# AHT20_DEMO_V1_5.net
KiCad netlist of a schematic drawn in Altium Designer
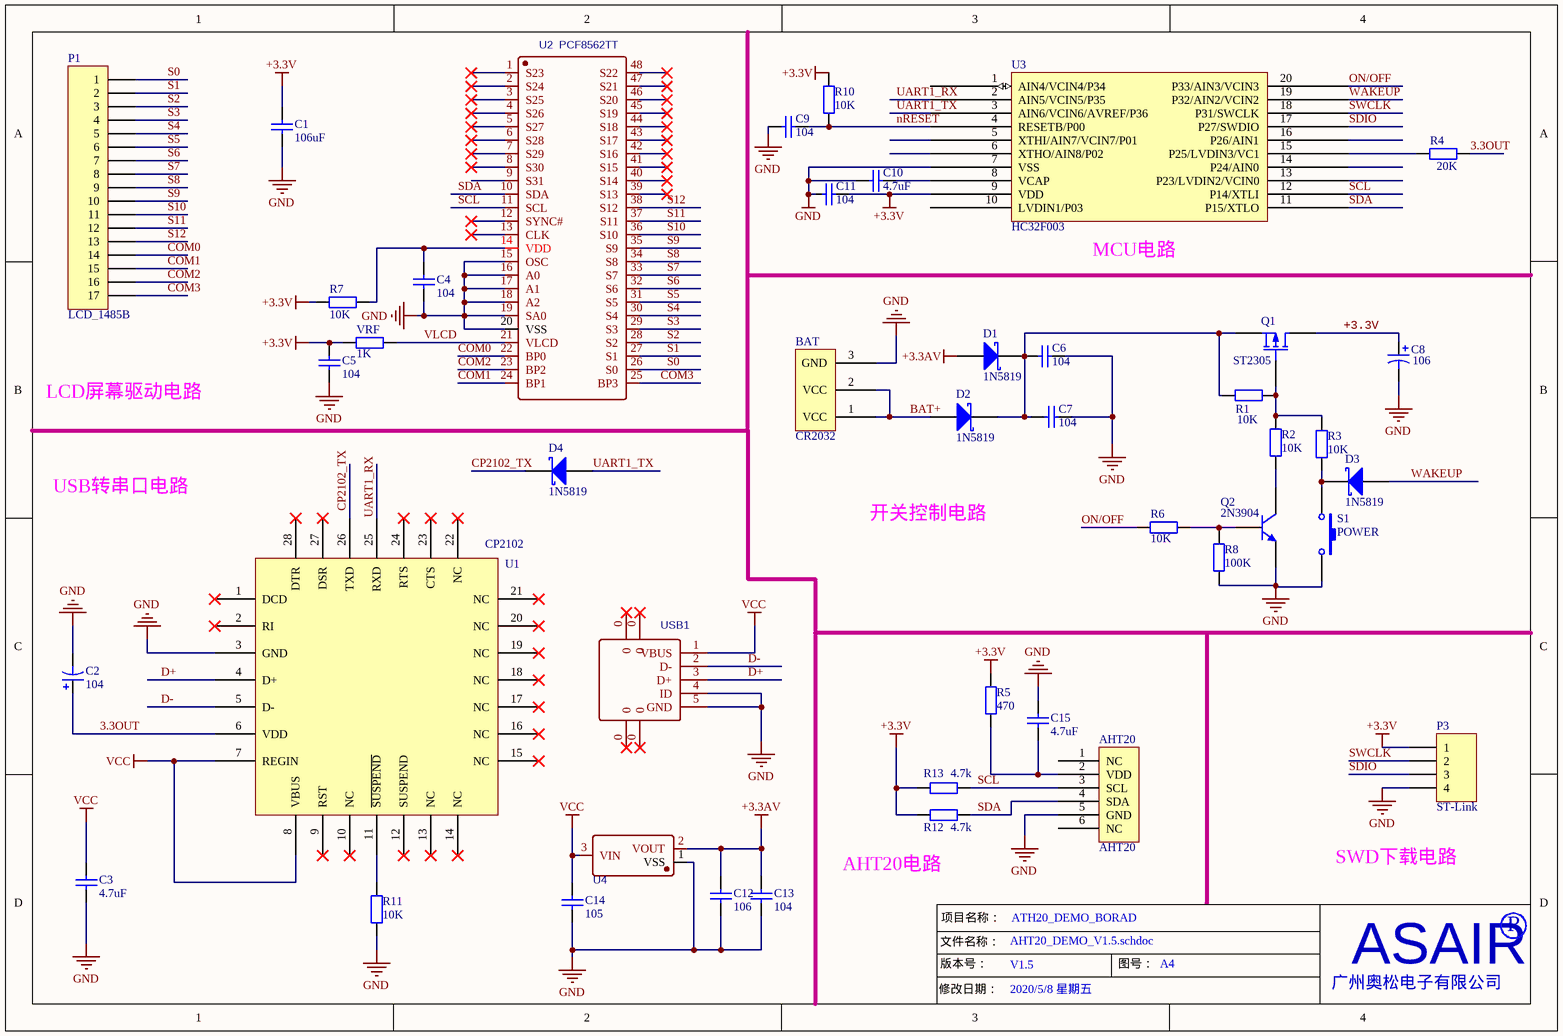
[diagram p0: AHT20_DEMO_V1.5.schdoc]

(export (version "E")
  (design (tool "Eeschema 10.0.6"))
  (components
    (comp (ref "AHT20") (value "AHT20") (footprint "AHT20") (libsource (lib "Schlib1") (part "AHT20")))
    (comp (ref "BAT") (value "CR2032") (footprint "CR2032-W") (libsource (lib "Schlib1") (part "CR2032")))
    (comp (ref "C1")
      (value "106uF")
      (footprint "0603C")
      (description "Capacitor")
      (fields (field (name "PUBLISHER") "Altium Limited"))
      (libsource (lib "Miscellaneous Devices") (part "Cap"))
    )
    (comp (ref "C2")
      (value "104")
      (footprint "0603c")
      (description "Polarized Capacitor (Radial)")
      (fields (field (name "PUBLISHER") "Altium Limited"))
      (libsource (lib "*") (part "Cap Pol1"))
    )
    (comp (ref "C3")
      (value "4.7uF")
      (footprint "0603C")
      (description "Capacitor")
      (fields (field (name "PUBLISHER") "Altium Limited"))
      (libsource (lib "Miscellaneous Devices") (part "Cap"))
    )
    (comp (ref "C4")
      (value "104")
      (footprint "0603C")
      (description "Capacitor")
      (fields (field (name "PUBLISHER") "Altium Limited"))
      (libsource (lib "Miscellaneous Devices") (part "Cap"))
    )
    (comp (ref "C5")
      (value "104")
      (footprint "0603C")
      (description "Capacitor")
      (fields (field (name "PUBLISHER") "Altium Limited"))
      (libsource (lib "Miscellaneous Devices") (part "Cap"))
    )
    (comp (ref "C6")
      (value "104")
      (footprint "0603C")
      (description "Capacitor")
      (fields (field (name "PUBLISHER") "Altium Limited"))
      (libsource (lib "Miscellaneous Devices") (part "Cap"))
    )
    (comp (ref "C7")
      (value "104")
      (footprint "0603C")
      (description "Capacitor")
      (fields (field (name "PUBLISHER") "Altium Limited"))
      (libsource (lib "Miscellaneous Devices") (part "Cap"))
    )
    (comp (ref "C8")
      (value "106")
      (footprint "0603c")
      (description "Polarized Capacitor (Radial)")
      (fields (field (name "PUBLISHER") "Altium Limited"))
      (libsource (lib "*") (part "Cap Pol1"))
    )
    (comp (ref "C9")
      (value "104")
      (footprint "0603C")
      (description "Capacitor")
      (fields (field (name "PUBLISHER") "Altium Limited"))
      (libsource (lib "Miscellaneous Devices") (part "Cap"))
    )
    (comp (ref "C10")
      (value "4.7uF")
      (footprint "0603C")
      (description "Capacitor")
      (fields (field (name "PUBLISHER") "Altium Limited"))
      (libsource (lib "Miscellaneous Devices") (part "Cap"))
    )
    (comp (ref "C11")
      (value "104")
      (footprint "0603C")
      (description "Capacitor")
      (fields (field (name "PUBLISHER") "Altium Limited"))
      (libsource (lib "Miscellaneous Devices") (part "Cap"))
    )
    (comp (ref "C12")
      (value "106")
      (footprint "0603C")
      (description "Capacitor")
      (fields (field (name "Comment") "104") (field (name "PUBLISHER") "Altium Limited"))
      (libsource (lib "Miscellaneous Devices") (part "Cap"))
    )
    (comp (ref "C13")
      (value "104")
      (footprint "0603C")
      (description "Capacitor")
      (fields (field (name "PUBLISHER") "Altium Limited"))
      (libsource (lib "Miscellaneous Devices") (part "Cap"))
    )
    (comp (ref "C14")
      (value "105")
      (footprint "0603C")
      (description "Capacitor")
      (fields (field (name "Comment") "104") (field (name "PUBLISHER") "Altium Limited"))
      (libsource (lib "Miscellaneous Devices") (part "Cap"))
    )
    (comp (ref "C15")
      (value "4.7uF")
      (footprint "0603C")
      (description "Capacitor")
      (fields (field (name "PUBLISHER") "Altium Limited"))
      (libsource (lib "Miscellaneous Devices") (part "Cap"))
    )
    (comp (ref "D1")
      (value "1N5819")
      (footprint "0805-LED")
      (description "Schottky Diode")
      (fields (field (name "PUBLISHER") "Altium Limited"))
      (libsource (lib "*") (part "D Schottky"))
    )
    (comp (ref "D2")
      (value "1N5819")
      (footprint "0805-LED")
      (description "Schottky Diode")
      (fields (field (name "PUBLISHER") "Altium Limited"))
      (libsource (lib "*") (part "D Schottky"))
    )
    (comp (ref "D3")
      (value "1N5819")
      (footprint "0805-LED")
      (description "Schottky Diode")
      (fields (field (name "PUBLISHER") "Altium Limited"))
      (libsource (lib "*") (part "D Schottky"))
    )
    (comp (ref "D4")
      (value "1N5819")
      (footprint "0805-LED")
      (description "Schottky Diode")
      (fields (field (name "PUBLISHER") "Altium Limited"))
      (libsource (lib "*") (part "D Schottky"))
    )
    (comp (ref "P1")
      (value "LCD_1485B")
      (footprint "LCD1485B")
      (description "Header, 17-Pin")
      (fields (field (name "PUBLISHER") "Altium Limited"))
      (libsource (lib "AW1485B") (part "LED1485B"))
    )
    (comp (ref "P3")
      (value "ST-Link")
      (footprint "DIP-5")
      (description "Header, 4-Pin")
      (fields (field (name "PUBLISHER") "Altium Limited"))
      (libsource (lib "*") (part "Header 4"))
    )
    (comp (ref "Q1")
      (value "ST2305")
      (footprint "SOt23")
      (description "P-Channel MOSFET")
      (fields (field (name "PUBLISHER") "Altium Limited"))
      (libsource (lib "Miscellaneous Devices") (part "MOSFET-P"))
    )
    (comp (ref "Q2")
      (value "2N3904")
      (footprint "SOt23")
      (description "NPN General Purpose Amplifier")
      (fields (field (name "PUBLISHER") "Altium Limited"))
      (libsource (lib "Miscellaneous Devices") (part "2N3904"))
    )
    (comp (ref "R1")
      (value "10K")
      (footprint "0603R")
      (description "Resistor")
      (fields (field (name "PUBLISHER") "Altium Limited"))
      (libsource (lib "") (part "Res2_6"))
    )
    (comp (ref "R2")
      (value "10K")
      (footprint "0603R")
      (description "Resistor")
      (fields (field (name "PUBLISHER") "Altium Limited"))
      (libsource (lib "") (part "Res2_5"))
    )
    (comp (ref "R3")
      (value "10K")
      (footprint "0603R")
      (description "Resistor")
      (fields (field (name "PUBLISHER") "Altium Limited"))
      (libsource (lib "") (part "Res2_5"))
    )
    (comp (ref "R4")
      (value "20K")
      (footprint "0603R")
      (description "Resistor")
      (fields (field (name "PUBLISHER") "Altium Limited"))
      (libsource (lib "") (part "Res2_1"))
    )
    (comp (ref "R5")
      (value "470")
      (footprint "0603R")
      (description "Resistor")
      (fields (field (name "PUBLISHER") "Altium Limited"))
      (libsource (lib "") (part "Res2_4"))
    )
    (comp (ref "R6")
      (value "10K")
      (footprint "0603R")
      (description "Resistor")
      (fields (field (name "PUBLISHER") "Altium Limited"))
      (libsource (lib "") (part "Res2_1"))
    )
    (comp (ref "R7")
      (value "10K")
      (footprint "0603R")
      (description "Resistor")
      (fields (field (name "PUBLISHER") "Altium Limited"))
      (libsource (lib "") (part "Res2_5"))
    )
    (comp (ref "R8")
      (value "100K")
      (footprint "0603R")
      (description "Resistor")
      (fields (field (name "PUBLISHER") "Altium Limited"))
      (libsource (lib "") (part "Res2_5"))
    )
    (comp (ref "R10")
      (value "10K")
      (footprint "0603R")
      (description "Resistor")
      (fields (field (name "PUBLISHER") "Altium Limited"))
      (libsource (lib "") (part "Res2_3"))
    )
    (comp (ref "R11")
      (value "10K")
      (footprint "0603R")
      (description "Resistor")
      (fields (field (name "PUBLISHER") "Altium Limited"))
      (libsource (lib "") (part "Res2_2"))
    )
    (comp (ref "R12")
      (value "4.7k")
      (footprint "0603R")
      (description "Resistor")
      (fields (field (name "PUBLISHER") "Altium Limited"))
      (libsource (lib "Miscellaneous Devices") (part "Res2"))
    )
    (comp (ref "R13")
      (value "4.7k")
      (footprint "0603R")
      (description "Resistor")
      (fields (field (name "PUBLISHER") "Altium Limited"))
      (libsource (lib "Miscellaneous Devices") (part "Res2"))
    )
    (comp (ref "S1")
      (value "POWER")
      (footprint "KEY")
      (description "Switch")
      (fields (field (name "PUBLISHER") "Altium Limited"))
      (libsource (lib "*") (part "SW-PB"))
    )
    (comp (ref "U1") (value "CP2102") (footprint "CP2102") (libsource (lib "RLM600") (part "CP2102_1")))
    (comp (ref "U2")
      (value "PCF8562TT")
      (footprint "PCF8562TT")
      (fields (field (name "BOM_SUPPLIER PART") "C52805"))
      (libsource (lib "altium-import") (part "root_0_PCF8562TT_"))
    )
    (comp (ref "U3")
      (value "HC32F003")
      (footprint "TSSOP20")
      (description "MCU")
      (libsource (lib "AF5010-V5.0") (part "HC32F003"))
    )
    (comp (ref "U4")
      (value "XC6206P282MR_C347374")
      (footprint "XC6206")
      (fields
        (field (name "BOM_SUPPLIER PART") "C347374")
        (field (name "BOM_MANUFACTURER PART") "XC6206P282MR")
        (field (name "CONTRIBUTOR") "LCSC")
      )
      (libsource (lib "altium-import") (part "root_2_XC6206P282MR_C347374_"))
    )
    (comp (ref "USB1")
      (value "micro 5P_C77238")
      (footprint "USB")
      (fields (field (name "BOM_SUPPLIER PART") "C77238") (field (name "CONTRIBUTOR") "立创EDA官方封装库"))
      (libsource (lib "altium-import") (part "root_0_mirrored_micro 5P_C77238_"))
    )
    (comp (ref "VRF")
      (value "1K")
      (footprint "0603R")
      (description "Resistor")
      (fields (field (name "PUBLISHER") "Altium Limited"))
      (libsource (lib "Miscellaneous Devices") (part "Res2"))
    )
  )
  (nets
    (net (code "1") (name "+3.3AV") (class "Default")
      (node (ref "C12") (pin "2") (pinfunction "2_2") (pintype "passive"))
      (node (ref "C13") (pin "2") (pinfunction "2_2") (pintype "passive"))
      (node (ref "D1") (pin "1") (pinfunction "A_1") (pintype "passive"))
      (node (ref "U4") (pin "2") (pinfunction "VOUT_2") (pintype "passive"))
    )
    (net (code "2") (name "+3.3V") (class "Default")
      (node (ref "C1") (pin "2") (pinfunction "2_2") (pintype "passive"))
      (node (ref "C11") (pin "2") (pinfunction "2_2") (pintype "passive"))
      (node (ref "C5") (pin "2") (pinfunction "2_2") (pintype "passive"))
      (node (ref "C8") (pin "1") (pinfunction "1_1") (pintype "passive"))
      (node (ref "P3") (pin "1") (pinfunction "1_1") (pintype "passive"))
      (node (ref "Q1") (pin "1") (pinfunction "D_1") (pintype "passive"))
      (node (ref "R10") (pin "1") (pinfunction "1_1") (pintype "passive"))
      (node (ref "R12") (pin "1") (pinfunction "1_1") (pintype "passive"))
      (node (ref "R13") (pin "1") (pinfunction "1_1") (pintype "passive"))
      (node (ref "R5") (pin "2") (pinfunction "2_2") (pintype "passive"))
      (node (ref "R7") (pin "2") (pinfunction "2_2") (pintype "passive"))
      (node (ref "U3") (pin "9") (pinfunction "VDD_9") (pintype "passive"))
      (node (ref "VRF") (pin "1") (pinfunction "1_1") (pintype "passive"))
    )
    (net (code "3") (name "/3.3OUT") (class "Default")
      (node (ref "C2") (pin "1") (pinfunction "1_1") (pintype "passive"))
      (node (ref "R4") (pin "2") (pinfunction "2_2") (pintype "passive"))
      (node (ref "U1") (pin "6") (pinfunction "VDD_6") (pintype "passive"))
    )
    (net (code "4") (name "/BAT+") (class "Default")
      (node (ref "BAT") (pin "1") (pinfunction "VCC_1") (pintype "passive"))
      (node (ref "BAT") (pin "2") (pinfunction "VCC_2") (pintype "passive"))
      (node (ref "D2") (pin "1") (pinfunction "A_1") (pintype "passive"))
    )
    (net (code "5") (name "/COM0") (class "Default")
      (node (ref "P1") (pin "14") (pinfunction "14_14") (pintype "passive"))
      (node (ref "U2") (pin "22") (pinfunction "BP0_22") (pintype "passive"))
    )
    (net (code "6") (name "/COM1") (class "Default")
      (node (ref "P1") (pin "15") (pinfunction "15_15") (pintype "passive"))
      (node (ref "U2") (pin "24") (pinfunction "BP1_24") (pintype "passive"))
    )
    (net (code "7") (name "/COM2") (class "Default")
      (node (ref "P1") (pin "16") (pinfunction "16_16") (pintype "passive"))
      (node (ref "U2") (pin "23") (pinfunction "BP2_23") (pintype "passive"))
    )
    (net (code "8") (name "/COM3") (class "Default")
      (node (ref "P1") (pin "17") (pinfunction "17_17") (pintype "passive"))
      (node (ref "U2") (pin "25") (pinfunction "BP3_25") (pintype "passive"))
    )
    (net (code "9") (name "/CP2102_TX") (class "Default")
      (node (ref "D4") (pin "2") (pinfunction "K_2") (pintype "passive"))
      (node (ref "U1") (pin "26") (pinfunction "TXD_26") (pintype "passive"))
    )
    (net (code "10") (name "/D+") (class "Default")
      (node (ref "U1") (pin "4") (pinfunction "D+_4") (pintype "passive"))
      (node (ref "USB1") (pin "3") (pinfunction "D+_3") (pintype "passive"))
    )
    (net (code "11") (name "/D-") (class "Default")
      (node (ref "U1") (pin "5") (pinfunction "D-_5") (pintype "passive"))
      (node (ref "USB1") (pin "2") (pinfunction "D-_2") (pintype "passive"))
    )
    (net (code "12") (name "/ON{slash}OFF") (class "Default")
      (node (ref "R6") (pin "1") (pinfunction "1_1") (pintype "passive"))
      (node (ref "U3") (pin "20") (pinfunction "P33/AIN3/VCIN3_20") (pintype "passive"))
    )
    (net (code "13") (name "/S0") (class "Default")
      (node (ref "P1") (pin "1") (pinfunction "1_1") (pintype "passive"))
      (node (ref "U2") (pin "26") (pinfunction "S0_26") (pintype "passive"))
    )
    (net (code "14") (name "/S1") (class "Default")
      (node (ref "P1") (pin "2") (pinfunction "2_2") (pintype "passive"))
      (node (ref "U2") (pin "27") (pinfunction "S1_27") (pintype "passive"))
    )
    (net (code "15") (name "/S2") (class "Default")
      (node (ref "P1") (pin "3") (pinfunction "3_3") (pintype "passive"))
      (node (ref "U2") (pin "28") (pinfunction "S2_28") (pintype "passive"))
    )
    (net (code "16") (name "/S3") (class "Default")
      (node (ref "P1") (pin "4") (pinfunction "4_4") (pintype "passive"))
      (node (ref "U2") (pin "29") (pinfunction "S3_29") (pintype "passive"))
    )
    (net (code "17") (name "/S4") (class "Default")
      (node (ref "P1") (pin "5") (pinfunction "5_5") (pintype "passive"))
      (node (ref "U2") (pin "30") (pinfunction "S4_30") (pintype "passive"))
    )
    (net (code "18") (name "/S5") (class "Default")
      (node (ref "P1") (pin "6") (pinfunction "6_6") (pintype "passive"))
      (node (ref "U2") (pin "31") (pinfunction "S5_31") (pintype "passive"))
    )
    (net (code "19") (name "/S6") (class "Default")
      (node (ref "P1") (pin "7") (pinfunction "7_7") (pintype "passive"))
      (node (ref "U2") (pin "32") (pinfunction "S6_32") (pintype "passive"))
    )
    (net (code "20") (name "/S7") (class "Default")
      (node (ref "P1") (pin "8") (pinfunction "8_8") (pintype "passive"))
      (node (ref "U2") (pin "33") (pinfunction "S7_33") (pintype "passive"))
    )
    (net (code "21") (name "/S8") (class "Default")
      (node (ref "P1") (pin "9") (pinfunction "9_9") (pintype "passive"))
      (node (ref "U2") (pin "34") (pinfunction "S8_34") (pintype "passive"))
    )
    (net (code "22") (name "/S9") (class "Default")
      (node (ref "P1") (pin "10") (pinfunction "10_10") (pintype "passive"))
      (node (ref "U2") (pin "35") (pinfunction "S9_35") (pintype "passive"))
    )
    (net (code "23") (name "/S10") (class "Default")
      (node (ref "P1") (pin "11") (pinfunction "11_11") (pintype "passive"))
      (node (ref "U2") (pin "36") (pinfunction "S10_36") (pintype "passive"))
    )
    (net (code "24") (name "/S11") (class "Default")
      (node (ref "P1") (pin "12") (pinfunction "12_12") (pintype "passive"))
      (node (ref "U2") (pin "37") (pinfunction "S11_37") (pintype "passive"))
    )
    (net (code "25") (name "/S12") (class "Default")
      (node (ref "P1") (pin "13") (pinfunction "13_13") (pintype "passive"))
      (node (ref "U2") (pin "38") (pinfunction "S12_38") (pintype "passive"))
    )
    (net (code "26") (name "/SCL") (class "Default")
      (node (ref "AHT20") (pin "3") (pinfunction "SCL_3") (pintype "passive"))
      (node (ref "R13") (pin "2") (pinfunction "2_2") (pintype "passive"))
      (node (ref "U2") (pin "11") (pinfunction "SCL_11") (pintype "passive"))
      (node (ref "U3") (pin "12") (pinfunction "P14/XTLI_12") (pintype "passive"))
    )
    (net (code "27") (name "/SDA") (class "Default")
      (node (ref "AHT20") (pin "4") (pinfunction "SDA_4") (pintype "passive"))
      (node (ref "R12") (pin "2") (pinfunction "2_2") (pintype "passive"))
      (node (ref "U2") (pin "10") (pinfunction "SDA_10") (pintype "passive"))
      (node (ref "U3") (pin "11") (pinfunction "P15/XTLO_11") (pintype "passive"))
    )
    (net (code "28") (name "/SDIO") (class "Default")
      (node (ref "P3") (pin "3") (pinfunction "3_3") (pintype "passive"))
      (node (ref "U3") (pin "17") (pinfunction "P27/SWDIO_17") (pintype "passive"))
    )
    (net (code "29") (name "/SWCLK") (class "Default")
      (node (ref "P3") (pin "2") (pinfunction "2_2") (pintype "passive"))
      (node (ref "U3") (pin "18") (pinfunction "P31/SWCLK_18") (pintype "passive"))
    )
    (net (code "30") (name "/UART1_RX") (class "Default")
      (node (ref "U1") (pin "25") (pinfunction "RXD_25") (pintype "passive"))
      (node (ref "U3") (pin "2") (pinfunction "AIN5/VCIN5/P35_2") (pintype "passive"))
    )
    (net (code "31") (name "/UART1_TX") (class "Default")
      (node (ref "D4") (pin "1") (pinfunction "A_1") (pintype "passive"))
      (node (ref "U3") (pin "3") (pinfunction "AIN6/VCIN6/AVREF/P36_3") (pintype "passive"))
    )
    (net (code "32") (name "/VLCD") (class "Default")
      (node (ref "U2") (pin "21") (pinfunction "VLCD_21") (pintype "passive"))
      (node (ref "VRF") (pin "2") (pinfunction "2_2") (pintype "passive"))
    )
    (net (code "33") (name "/WAKEUP") (class "Default")
      (node (ref "D3") (pin "1") (pinfunction "A_1") (pintype "passive"))
      (node (ref "U3") (pin "19") (pinfunction "P32/AIN2/VCIN2_19") (pintype "passive"))
    )
    (net (code "34") (name "/nRESET") (class "Default")
      (node (ref "C9") (pin "2") (pinfunction "2_2") (pintype "passive"))
      (node (ref "R10") (pin "2") (pinfunction "2_2") (pintype "passive"))
      (node (ref "U3") (pin "4") (pinfunction "RESETB/P00_4") (pintype "passive"))
    )
    (net (code "35") (name "GND") (class "Default")
      (node (ref "AHT20") (pin "5") (pinfunction "GND_5") (pintype "passive"))
      (node (ref "BAT") (pin "3") (pinfunction "GND_3") (pintype "passive"))
      (node (ref "C1") (pin "1") (pinfunction "1_1") (pintype "passive"))
      (node (ref "C10") (pin "1") (pinfunction "1_1") (pintype "passive"))
      (node (ref "C11") (pin "1") (pinfunction "1_1") (pintype "passive"))
      (node (ref "C12") (pin "1") (pinfunction "1_1") (pintype "passive"))
      (node (ref "C13") (pin "1") (pinfunction "1_1") (pintype "passive"))
      (node (ref "C14") (pin "1") (pinfunction "1_1") (pintype "passive"))
      (node (ref "C15") (pin "1") (pinfunction "1_1") (pintype "passive"))
      (node (ref "C2") (pin "2") (pinfunction "2_2") (pintype "passive"))
      (node (ref "C3") (pin "1") (pinfunction "1_1") (pintype "passive"))
      (node (ref "C4") (pin "1") (pinfunction "1_1") (pintype "passive"))
      (node (ref "C5") (pin "1") (pinfunction "1_1") (pintype "passive"))
      (node (ref "C6") (pin "2") (pinfunction "2_2") (pintype "passive"))
      (node (ref "C7") (pin "2") (pinfunction "2_2") (pintype "passive"))
      (node (ref "C8") (pin "2") (pinfunction "2_2") (pintype "passive"))
      (node (ref "C9") (pin "1") (pinfunction "1_1") (pintype "passive"))
      (node (ref "P3") (pin "4") (pinfunction "4_4") (pintype "passive"))
      (node (ref "Q2") (pin "1") (pinfunction "E_1") (pintype "passive"))
      (node (ref "R11") (pin "2") (pinfunction "2_2") (pintype "passive"))
      (node (ref "R8") (pin "2") (pinfunction "2_2") (pintype "passive"))
      (node (ref "S1") (pin "2") (pinfunction "2_2") (pintype "passive"))
      (node (ref "U1") (pin "3") (pinfunction "GND_3") (pintype "passive"))
      (node (ref "U2") (pin "15") (pinfunction "OSC_15") (pintype "passive"))
      (node (ref "U2") (pin "16") (pinfunction "A0_16") (pintype "passive"))
      (node (ref "U2") (pin "17") (pinfunction "A1_17") (pintype "passive"))
      (node (ref "U2") (pin "18") (pinfunction "A2_18") (pintype "passive"))
      (node (ref "U2") (pin "19") (pinfunction "SA0_19") (pintype "passive"))
      (node (ref "U2") (pin "20") (pinfunction "VSS_20") (pintype "passive"))
      (node (ref "U3") (pin "7") (pinfunction "VSS_7") (pintype "passive"))
      (node (ref "U4") (pin "1") (pinfunction "VSS_1") (pintype "passive"))
      (node (ref "USB1") (pin "4") (pinfunction "ID_4") (pintype "passive"))
      (node (ref "USB1") (pin "5") (pinfunction "GND_5") (pintype "passive"))
    )
    (net (code "36") (name "Net-(AHT20-VDD)") (class "Default")
      (node (ref "AHT20") (pin "2") (pinfunction "VDD_2") (pintype "passive"))
      (node (ref "C15") (pin "2") (pinfunction "2_2") (pintype "passive"))
      (node (ref "R5") (pin "1") (pinfunction "1_1") (pintype "passive"))
    )
    (net (code "37") (name "Net-(D1-K)") (class "Default")
      (node (ref "C6") (pin "1") (pinfunction "1_1") (pintype "passive"))
      (node (ref "C7") (pin "1") (pinfunction "1_1") (pintype "passive"))
      (node (ref "D1") (pin "2") (pinfunction "K_2") (pintype "passive"))
      (node (ref "D2") (pin "2") (pinfunction "K_2") (pintype "passive"))
      (node (ref "Q1") (pin "3") (pinfunction "S_3") (pintype "passive"))
      (node (ref "R1") (pin "2") (pinfunction "2_2") (pintype "passive"))
    )
    (net (code "38") (name "Net-(D3-K)") (class "Default")
      (node (ref "D3") (pin "2") (pinfunction "K_2") (pintype "passive"))
      (node (ref "R3") (pin "2") (pinfunction "2_2") (pintype "passive"))
      (node (ref "S1") (pin "1") (pinfunction "1_1") (pintype "passive"))
    )
    (net (code "39") (name "Net-(Q1-G)") (class "Default")
      (node (ref "Q1") (pin "2") (pinfunction "G_2") (pintype "passive"))
      (node (ref "R1") (pin "1") (pinfunction "1_1") (pintype "passive"))
      (node (ref "R2") (pin "1") (pinfunction "1_1") (pintype "passive"))
      (node (ref "R3") (pin "1") (pinfunction "1_1") (pintype "passive"))
    )
    (net (code "40") (name "Net-(Q2-B)") (class "Default")
      (node (ref "Q2") (pin "2") (pinfunction "B_2") (pintype "passive"))
      (node (ref "R6") (pin "2") (pinfunction "2_2") (pintype "passive"))
      (node (ref "R8") (pin "1") (pinfunction "1_1") (pintype "passive"))
    )
    (net (code "41") (name "Net-(Q2-C)") (class "Default")
      (node (ref "Q2") (pin "3") (pinfunction "C_3") (pintype "passive"))
      (node (ref "R2") (pin "2") (pinfunction "2_2") (pintype "passive"))
    )
    (net (code "42") (name "Net-(U1-~{SUSPEND})") (class "Default")
      (node (ref "R11") (pin "1") (pinfunction "1_1") (pintype "passive"))
      (node (ref "U1") (pin "11") (pinfunction "~{SUSPEND}_11") (pintype "passive"))
    )
    (net (code "43") (name "Net-(U2-VDD)") (class "Default")
      (node (ref "C4") (pin "2") (pinfunction "2_2") (pintype "passive"))
      (node (ref "R7") (pin "1") (pinfunction "1_1") (pintype "passive"))
      (node (ref "U2") (pin "14") (pinfunction "VDD_14") (pintype "passive"))
    )
    (net (code "44") (name "Net-(U3-P25{slash}LVDIN3{slash}VC1)") (class "Default")
      (node (ref "R4") (pin "1") (pinfunction "1_1") (pintype "passive"))
      (node (ref "U3") (pin "15") (pinfunction "P25/LVDIN3/VC1_15") (pintype "passive"))
    )
    (net (code "45") (name "Net-(U3-VCAP)") (class "Default")
      (node (ref "C10") (pin "2") (pinfunction "2_2") (pintype "passive"))
      (node (ref "U3") (pin "8") (pinfunction "VCAP_8") (pintype "passive"))
    )
    (net (code "46") (name "VCC") (class "Default")
      (node (ref "C14") (pin "2") (pinfunction "2_2") (pintype "passive"))
      (node (ref "C3") (pin "2") (pinfunction "2_2") (pintype "passive"))
      (node (ref "U1") (pin "7") (pinfunction "REGIN_7") (pintype "passive"))
      (node (ref "U1") (pin "8") (pinfunction "VBUS_8") (pintype "passive"))
      (node (ref "U4") (pin "3") (pinfunction "VIN_3") (pintype "passive"))
      (node (ref "USB1") (pin "1") (pinfunction "VBUS_1") (pintype "passive"))
    )
    (net (code "47") (name "unconnected-(AHT20-NC-Pad1)") (class "Default")
      (node (ref "AHT20") (pin "1") (pinfunction "NC_1") (pintype "passive"))
    )
    (net (code "48") (name "unconnected-(AHT20-NC-Pad6)") (class "Default")
      (node (ref "AHT20") (pin "6") (pinfunction "NC_6") (pintype "passive"))
    )
    (net (code "49") (name "unconnected-(U1-CTS-Pad23)") (class "Default")
      (node (ref "U1") (pin "23") (pinfunction "CTS_23") (pintype "passive+no_connect"))
    )
    (net (code "50") (name "unconnected-(U1-DCD-Pad1)") (class "Default")
      (node (ref "U1") (pin "1") (pinfunction "DCD_1") (pintype "passive+no_connect"))
    )
    (net (code "51") (name "unconnected-(U1-DSR-Pad27)") (class "Default")
      (node (ref "U1") (pin "27") (pinfunction "DSR_27") (pintype "passive+no_connect"))
    )
    (net (code "52") (name "unconnected-(U1-DTR-Pad28)") (class "Default")
      (node (ref "U1") (pin "28") (pinfunction "DTR_28") (pintype "passive+no_connect"))
    )
    (net (code "53") (name "unconnected-(U1-NC-Pad10)") (class "Default")
      (node (ref "U1") (pin "10") (pinfunction "NC_10") (pintype "passive+no_connect"))
    )
    (net (code "54") (name "unconnected-(U1-NC-Pad13)") (class "Default")
      (node (ref "U1") (pin "13") (pinfunction "NC_13") (pintype "passive+no_connect"))
    )
    (net (code "55") (name "unconnected-(U1-NC-Pad14)") (class "Default")
      (node (ref "U1") (pin "14") (pinfunction "NC_14") (pintype "passive+no_connect"))
    )
    (net (code "56") (name "unconnected-(U1-NC-Pad15)") (class "Default")
      (node (ref "U1") (pin "15") (pinfunction "NC_15") (pintype "passive+no_connect"))
    )
    (net (code "57") (name "unconnected-(U1-NC-Pad16)") (class "Default")
      (node (ref "U1") (pin "16") (pinfunction "NC_16") (pintype "passive+no_connect"))
    )
    (net (code "58") (name "unconnected-(U1-NC-Pad17)") (class "Default")
      (node (ref "U1") (pin "17") (pinfunction "NC_17") (pintype "passive+no_connect"))
    )
    (net (code "59") (name "unconnected-(U1-NC-Pad18)") (class "Default")
      (node (ref "U1") (pin "18") (pinfunction "NC_18") (pintype "passive+no_connect"))
    )
    (net (code "60") (name "unconnected-(U1-NC-Pad19)") (class "Default")
      (node (ref "U1") (pin "19") (pinfunction "NC_19") (pintype "passive+no_connect"))
    )
    (net (code "61") (name "unconnected-(U1-NC-Pad20)") (class "Default")
      (node (ref "U1") (pin "20") (pinfunction "NC_20") (pintype "passive+no_connect"))
    )
    (net (code "62") (name "unconnected-(U1-NC-Pad21)") (class "Default")
      (node (ref "U1") (pin "21") (pinfunction "NC_21") (pintype "passive+no_connect"))
    )
    (net (code "63") (name "unconnected-(U1-NC-Pad22)") (class "Default")
      (node (ref "U1") (pin "22") (pinfunction "NC_22") (pintype "passive+no_connect"))
    )
    (net (code "64") (name "unconnected-(U1-RI-Pad2)") (class "Default")
      (node (ref "U1") (pin "2") (pinfunction "RI_2") (pintype "passive+no_connect"))
    )
    (net (code "65") (name "unconnected-(U1-RST-Pad9)") (class "Default")
      (node (ref "U1") (pin "9") (pinfunction "RST_9") (pintype "passive+no_connect"))
    )
    (net (code "66") (name "unconnected-(U1-RTS-Pad24)") (class "Default")
      (node (ref "U1") (pin "24") (pinfunction "RTS_24") (pintype "passive+no_connect"))
    )
    (net (code "67") (name "unconnected-(U1-SUSPEND-Pad12)") (class "Default")
      (node (ref "U1") (pin "12") (pinfunction "SUSPEND_12") (pintype "passive+no_connect"))
    )
    (net (code "68") (name "unconnected-(U2-CLK-Pad13)") (class "Default")
      (node (ref "U2") (pin "13") (pinfunction "CLK_13") (pintype "passive+no_connect"))
    )
    (net (code "69") (name "unconnected-(U2-S13-Pad39)") (class "Default")
      (node (ref "U2") (pin "39") (pinfunction "S13_39") (pintype "passive+no_connect"))
    )
    (net (code "70") (name "unconnected-(U2-S14-Pad40)") (class "Default")
      (node (ref "U2") (pin "40") (pinfunction "S14_40") (pintype "passive+no_connect"))
    )
    (net (code "71") (name "unconnected-(U2-S15-Pad41)") (class "Default")
      (node (ref "U2") (pin "41") (pinfunction "S15_41") (pintype "passive+no_connect"))
    )
    (net (code "72") (name "unconnected-(U2-S16-Pad42)") (class "Default")
      (node (ref "U2") (pin "42") (pinfunction "S16_42") (pintype "passive+no_connect"))
    )
    (net (code "73") (name "unconnected-(U2-S17-Pad43)") (class "Default")
      (node (ref "U2") (pin "43") (pinfunction "S17_43") (pintype "passive+no_connect"))
    )
    (net (code "74") (name "unconnected-(U2-S18-Pad44)") (class "Default")
      (node (ref "U2") (pin "44") (pinfunction "S18_44") (pintype "passive+no_connect"))
    )
    (net (code "75") (name "unconnected-(U2-S19-Pad45)") (class "Default")
      (node (ref "U2") (pin "45") (pinfunction "S19_45") (pintype "passive+no_connect"))
    )
    (net (code "76") (name "unconnected-(U2-S20-Pad46)") (class "Default")
      (node (ref "U2") (pin "46") (pinfunction "S20_46") (pintype "passive+no_connect"))
    )
    (net (code "77") (name "unconnected-(U2-S21-Pad47)") (class "Default")
      (node (ref "U2") (pin "47") (pinfunction "S21_47") (pintype "passive+no_connect"))
    )
    (net (code "78") (name "unconnected-(U2-S22-Pad48)") (class "Default")
      (node (ref "U2") (pin "48") (pinfunction "S22_48") (pintype "passive+no_connect"))
    )
    (net (code "79") (name "unconnected-(U2-S23-Pad1)") (class "Default")
      (node (ref "U2") (pin "1") (pinfunction "S23_1") (pintype "passive+no_connect"))
    )
    (net (code "80") (name "unconnected-(U2-S24-Pad2)") (class "Default")
      (node (ref "U2") (pin "2") (pinfunction "S24_2") (pintype "passive+no_connect"))
    )
    (net (code "81") (name "unconnected-(U2-S25-Pad3)") (class "Default")
      (node (ref "U2") (pin "3") (pinfunction "S25_3") (pintype "passive+no_connect"))
    )
    (net (code "82") (name "unconnected-(U2-S26-Pad4)") (class "Default")
      (node (ref "U2") (pin "4") (pinfunction "S26_4") (pintype "passive+no_connect"))
    )
    (net (code "83") (name "unconnected-(U2-S27-Pad5)") (class "Default")
      (node (ref "U2") (pin "5") (pinfunction "S27_5") (pintype "passive+no_connect"))
    )
    (net (code "84") (name "unconnected-(U2-S28-Pad6)") (class "Default")
      (node (ref "U2") (pin "6") (pinfunction "S28_6") (pintype "passive+no_connect"))
    )
    (net (code "85") (name "unconnected-(U2-S29-Pad7)") (class "Default")
      (node (ref "U2") (pin "7") (pinfunction "S29_7") (pintype "passive+no_connect"))
    )
    (net (code "86") (name "unconnected-(U2-S30-Pad8)") (class "Default")
      (node (ref "U2") (pin "8") (pinfunction "S30_8") (pintype "passive+no_connect"))
    )
    (net (code "87") (name "unconnected-(U2-S31-Pad9)") (class "Default")
      (node (ref "U2") (pin "9") (pinfunction "S31_9") (pintype "passive"))
    )
    (net (code "88") (name "unconnected-(U2-SYNC#-Pad12)") (class "Default")
      (node (ref "U2") (pin "12") (pinfunction "SYNC#_12") (pintype "passive+no_connect"))
    )
    (net (code "89") (name "unconnected-(U3-AIN4{slash}VCIN4{slash}P34-Pad1)") (class "Default")
      (node (ref "U3") (pin "1") (pinfunction "AIN4/VCIN4/P34_1") (pintype "bidirectional"))
    )
    (net (code "90") (name "unconnected-(U3-LVDIN1{slash}P03-Pad10)") (class "Default")
      (node (ref "U3") (pin "10") (pinfunction "LVDIN1/P03_10") (pintype "passive"))
    )
    (net (code "91") (name "unconnected-(U3-P23{slash}LVDIN2{slash}VCIN0-Pad13)") (class "Default")
      (node (ref "U3") (pin "13") (pinfunction "P23/LVDIN2/VCIN0_13") (pintype "passive"))
    )
    (net (code "92") (name "unconnected-(U3-P24{slash}AIN0-Pad14)") (class "Default")
      (node (ref "U3") (pin "14") (pinfunction "P24/AIN0_14") (pintype "passive"))
    )
    (net (code "93") (name "unconnected-(U3-P26{slash}AIN1-Pad16)") (class "Default")
      (node (ref "U3") (pin "16") (pinfunction "P26/AIN1_16") (pintype "passive"))
    )
    (net (code "94") (name "unconnected-(U3-XTHI{slash}AIN7{slash}VCIN7{slash}P01-Pad5)") (class "Default")
      (node (ref "U3") (pin "5") (pinfunction "XTHI/AIN7/VCIN7/P01_5") (pintype "passive"))
    )
    (net (code "95") (name "unconnected-(U3-XTHO{slash}AIN8{slash}P02-Pad6)") (class "Default")
      (node (ref "U3") (pin "6") (pinfunction "XTHO/AIN8/P02_6") (pintype "passive"))
    )
    (net (code "96") (name "unconnected-(USB1-Pad0)") (class "Default")
      (node (ref "USB1") (pin "0") (pinfunction "0_0") (pintype "passive+no_connect"))
    )
    (net (code "97") (name "unconnected-(USB1-Pad0)_1") (class "Default")
      (node (ref "USB1") (pin "0") (pinfunction "0_0") (pintype "passive+no_connect"))
    )
    (net (code "98") (name "unconnected-(USB1-Pad0)_2") (class "Default")
      (node (ref "USB1") (pin "0") (pinfunction "0_0") (pintype "passive+no_connect"))
    )
    (net (code "99") (name "unconnected-(USB1-Pad0)_3") (class "Default")
      (node (ref "USB1") (pin "0") (pinfunction "0_0") (pintype "passive+no_connect"))
    )
  )
)
